# PWR-CONNS.net
KiCad netlist of a schematic drawn in Altium Designer
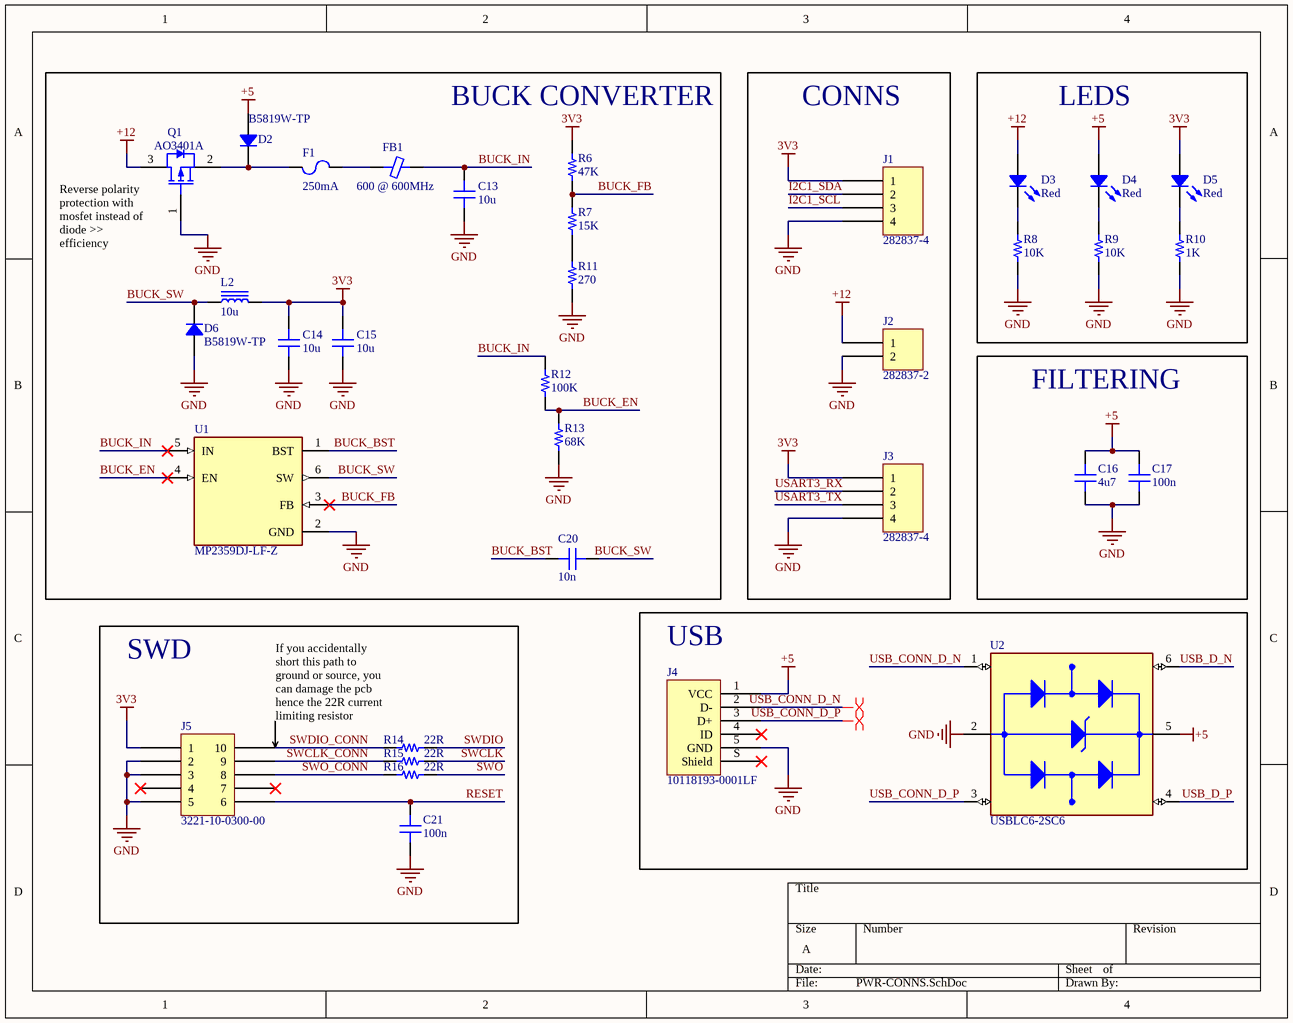
[diagram p0: PWR-CONNS.SchDoc]

(export (version "E")
  (design (tool "Eeschema 10.0.6"))
  (components
    (comp (ref "C13")
      (value "10u")
      (footprint "CAP 0805_2012")
      (description "CAP CER 2200PF 16V X7R 0805")
      (fields (field (name "PART NUMBER") "C0805C222K4RAC7800") (field (name "MANUFACTURER") "KEMET"))
      (libsource (lib "Celestial Altium Library - altium_library") (part "Capacitor"))
    )
    (comp (ref "C14")
      (value "10u")
      (footprint "CAP 0805_2012")
      (description "CAP CER 2200PF 16V X7R 0805")
      (fields (field (name "PART NUMBER") "C0805C222K4RAC7800") (field (name "MANUFACTURER") "KEMET"))
      (libsource (lib "Celestial Altium Library - altium_library") (part "Capacitor"))
    )
    (comp (ref "C15")
      (value "10u")
      (footprint "CAP 0805_2012")
      (description "CAP CER 2200PF 16V X7R 0805")
      (fields (field (name "PART NUMBER") "C0805C222K4RAC7800") (field (name "MANUFACTURER") "KEMET"))
      (libsource (lib "Celestial Altium Library - altium_library") (part "Capacitor"))
    )
    (comp (ref "C16")
      (value "4u7")
      (footprint "CAP 0603_1608")
      (description "CAP CER SMD 0603 .1UF 5% X7R 16V")
      (fields (field (name "PART NUMBER") "C0603C104J4RAC7013") (field (name "MANUFACTURER") "KEMET"))
      (libsource (lib "Celestial Altium Library - altium_library") (part "Capacitor"))
    )
    (comp (ref "C17")
      (value "100n")
      (footprint "CAP 0603_1608")
      (description "CAP CER SMD 0603 .1UF 5% X7R 16V")
      (fields (field (name "PART NUMBER") "C0603C104J4RAC7013") (field (name "MANUFACTURER") "KEMET"))
      (libsource (lib "Celestial Altium Library - altium_library") (part "Capacitor"))
    )
    (comp (ref "C20")
      (value "10n")
      (footprint "CAP 0805_2012")
      (description "CAP CER 2200PF 16V X7R 0805")
      (fields (field (name "PART NUMBER") "C0805C222K4RAC7800") (field (name "MANUFACTURER") "KEMET"))
      (libsource (lib "Celestial Altium Library - altium_library") (part "Capacitor"))
    )
    (comp (ref "C21")
      (value "100n")
      (footprint "CAP 0603_1608")
      (description "CAP CER SMD 0603 .1UF 5% X7R 16V")
      (fields (field (name "PART NUMBER") "C0603C104J4RAC7013") (field (name "MANUFACTURER") "KEMET"))
      (libsource (lib "Celestial Altium Library - altium_library") (part "Capacitor"))
    )
    (comp (ref "D2")
      (value "B5819W-TP")
      (footprint "SOD-123")
      (description "DIODE SCHOTTKY 40V 1A SOD123")
      (fields (field (name "MANUFACTURER") "Micro Commercial Co"))
      (libsource (lib "Celestial Altium Library - altium_library") (part "Diode"))
    )
    (comp (ref "D3")
      (value "Red")
      (footprint "LED 0603_1608 RED")
      (description "LED RED 0603")
      (fields (field (name "PART NUMBER") "APT1608SEC/J3-AMT") (field (name "MANUFACTURER") "Kingbright"))
      (libsource (lib "Celestial Altium Library - altium_library") (part "LED"))
    )
    (comp (ref "D4")
      (value "Red")
      (footprint "LED 0603_1608 RED")
      (description "LED RED 0603")
      (fields (field (name "PART NUMBER") "APT1608SEC/J3-AMT") (field (name "MANUFACTURER") "Kingbright"))
      (libsource (lib "Celestial Altium Library - altium_library") (part "LED"))
    )
    (comp (ref "D5")
      (value "Red")
      (footprint "LED 0603_1608 RED")
      (description "LED RED 0603")
      (fields (field (name "PART NUMBER") "APT1608SEC/J3-AMT") (field (name "MANUFACTURER") "Kingbright"))
      (libsource (lib "Celestial Altium Library - altium_library") (part "LED"))
    )
    (comp (ref "D6")
      (value "B5819W-TP")
      (footprint "SOD-123")
      (description "DIODE SCHOTTKY 40V 1A SOD123")
      (fields (field (name "MANUFACTURER") "Micro Commercial Co"))
      (libsource (lib "Celestial Altium Library - altium_library") (part "Diode"))
    )
    (comp (ref "F1")
      (value "250mA")
      (footprint "FUSE 1206_3216 0.6MM")
      (description "FUSE BOARD MNT 500MA 63VDC 1206")
      (fields (field (name "PART NUMBER") "SF-1206FP050-2") (field (name "MANUFACTURER") "Bourns Inc."))
      (libsource (lib "Celestial Altium Library - altium_library") (part "MOUNTED FUSE"))
    )
    (comp (ref "FB1")
      (value "600 @ 600MHz")
      (footprint "FER 0402_1005")
      (description "FERRITE BEAD 600 OHM 0402 1LN")
      (fields (field (name "PART NUMBER") "Z0402C601ESMST") (field (name "MANUFACTURER") "KEMET"))
      (libsource (lib "Celestial Altium Library - altium_library") (part "Ferrite Chip"))
    )
    (comp (ref "J1")
      (value "282837-4")
      (footprint "TE 282837-4")
      (description "TERM BLK 4P SIDE ENT 5.08MM PCB")
      (fields (field (name "MANUFACTURER") "TE Connectivity AMP Connectors") (field (name "VOLTAGE") "300 V"))
      (libsource (lib "Celestial Altium Library - altium_library") (part "4 Pin"))
    )
    (comp (ref "J2")
      (value "282837-2")
      (footprint "TE 282837-2")
      (description "TERM BLK 2P SIDE ENT 5.08MM PCB")
      (fields (field (name "MANUFACTURER") "TE Connectivity AMP Connectors") (field (name "VOLTAGE") "300 V"))
      (libsource (lib "Celestial Altium Library - altium_library") (part "2 Pin"))
    )
    (comp (ref "J3")
      (value "282837-4")
      (footprint "TE 282837-4")
      (description "TERM BLK 4P SIDE ENT 5.08MM PCB")
      (fields (field (name "MANUFACTURER") "TE Connectivity AMP Connectors") (field (name "VOLTAGE") "300 V"))
      (libsource (lib "Celestial Altium Library - altium_library") (part "4 Pin"))
    )
    (comp (ref "J4")
      (value "10118193-0001LF")
      (footprint "FCI USB 10118193-0001LF")
      (description "CONN RCPT USB2.0 MICRO B SMD R/A")
      (fields (field (name "MANUFACTURER") "Amphenol ICC (FCI)"))
      (libsource (lib "Celestial Altium Library - altium_library") (part "USB 2.0 Type B Micro"))
    )
    (comp (ref "J5")
      (value "3221-10-0300-00")
      (footprint "CNC TECH 3221-10-0300-00")
      (description "CONN HEADER SMD 10POS 1.27MM")
      (fields (field (name "MANUFACTURER") "CNC Tech"))
      (libsource (lib "Celestial Altium Library - altium_library") (part "2x5 Pin"))
    )
    (comp (ref "L2")
      (value "10u")
      (footprint "BOURNS SRP5030T")
      (description "FIXED IND 10UH 2.75A 128MOHM SMD")
      (fields (field (name "PART NUMBER") "SRP5030T-100M") (field (name "MANUFACTURER") "Bourns Inc."))
      (libsource (lib "Celestial Altium Library - altium_library") (part "Inductor"))
    )
    (comp (ref "Q1")
      (value "AO3401A")
      (footprint "AO-SOT-23-3L_V")
      (description "P-Channel MOSFET, 30 V, 4 A, -55 to 150 degC, 3-Pin SOT-23-3L, RoHS, Tape and Reel")
      (fields (field (name "MANUFACTURER") "Alpha and Omega"))
      (libsource (lib "Altium Content Vault") (part "PEMOS-GSD-3"))
    )
    (comp (ref "R6")
      (value "47K")
      (footprint "RES 0603_1608")
      (description "RES SMD 47 OHM 1% 1/10W 0603")
      (fields (field (name "PART NUMBER") "AC0603FR-0747RL") (field (name "MANUFACTURER") "Yageo"))
      (libsource (lib "Celestial Altium Library - altium_library") (part "Resistor"))
    )
    (comp (ref "R7")
      (value "15K")
      (footprint "RES 0603_1608")
      (description "RES SMD 47 OHM 1% 1/10W 0603")
      (fields (field (name "PART NUMBER") "AC0603FR-0747RL") (field (name "MANUFACTURER") "Yageo"))
      (libsource (lib "Celestial Altium Library - altium_library") (part "Resistor"))
    )
    (comp (ref "R8")
      (value "10K")
      (footprint "RES 0603_1608")
      (description "RES SMD 47 OHM 1% 1/10W 0603")
      (fields (field (name "PART NUMBER") "AC0603FR-0747RL") (field (name "MANUFACTURER") "Yageo"))
      (libsource (lib "Celestial Altium Library - altium_library") (part "Resistor"))
    )
    (comp (ref "R9")
      (value "10K")
      (footprint "RES 0603_1608")
      (description "RES SMD 47 OHM 1% 1/10W 0603")
      (fields (field (name "PART NUMBER") "AC0603FR-0747RL") (field (name "MANUFACTURER") "Yageo"))
      (libsource (lib "Celestial Altium Library - altium_library") (part "Resistor"))
    )
    (comp (ref "R10")
      (value "1K")
      (footprint "RES 0603_1608")
      (description "RES SMD 47 OHM 1% 1/10W 0603")
      (fields (field (name "PART NUMBER") "AC0603FR-0747RL") (field (name "MANUFACTURER") "Yageo"))
      (libsource (lib "Celestial Altium Library - altium_library") (part "Resistor"))
    )
    (comp (ref "R11")
      (value "270")
      (footprint "RES 0603_1608")
      (description "RES SMD 47 OHM 1% 1/10W 0603")
      (fields (field (name "PART NUMBER") "AC0603FR-0747RL") (field (name "MANUFACTURER") "Yageo"))
      (libsource (lib "Celestial Altium Library - altium_library") (part "Resistor"))
    )
    (comp (ref "R12")
      (value "100K")
      (footprint "RES 0603_1608")
      (description "RES SMD 47 OHM 1% 1/10W 0603")
      (fields (field (name "PART NUMBER") "AC0603FR-0747RL") (field (name "MANUFACTURER") "Yageo"))
      (libsource (lib "Celestial Altium Library - altium_library") (part "Resistor"))
    )
    (comp (ref "R13")
      (value "68K")
      (footprint "RES 0603_1608")
      (description "RES SMD 47 OHM 1% 1/10W 0603")
      (fields (field (name "PART NUMBER") "AC0603FR-0747RL") (field (name "MANUFACTURER") "Yageo"))
      (libsource (lib "Celestial Altium Library - altium_library") (part "Resistor"))
    )
    (comp (ref "R14")
      (value "22R")
      (footprint "RES 0603_1608")
      (description "RES SMD 47 OHM 1% 1/10W 0603")
      (fields (field (name "PART NUMBER") "AC0603FR-0747RL") (field (name "MANUFACTURER") "Yageo"))
      (libsource (lib "Celestial Altium Library - altium_library") (part "Resistor"))
    )
    (comp (ref "R15")
      (value "22R")
      (footprint "RES 0603_1608")
      (description "RES SMD 47 OHM 1% 1/10W 0603")
      (fields (field (name "PART NUMBER") "AC0603FR-0747RL") (field (name "MANUFACTURER") "Yageo"))
      (libsource (lib "Celestial Altium Library - altium_library") (part "Resistor"))
    )
    (comp (ref "R16")
      (value "22R")
      (footprint "RES 0603_1608")
      (description "RES SMD 47 OHM 1% 1/10W 0603")
      (fields (field (name "PART NUMBER") "AC0603FR-0747RL") (field (name "MANUFACTURER") "Yageo"))
      (libsource (lib "Celestial Altium Library - altium_library") (part "Resistor"))
    )
    (comp (ref "U1")
      (value "MP2359DJ-LF-Z")
      (footprint "SOT95P280X100-6N")
      (description "Buck Switching Regulator IC Positive Adjustable 0.81V 1 Output 1.2A SOT-23-6 Thin, TSOT-23-6")
      (fields (field (name "MF") "Monolithic Power"))
      (libsource (lib "MP2359DJ-LF-Z") (part "MP2359DJ-LF-Z"))
    )
    (comp (ref "U2")
      (value "USBLC6-2SC6")
      (footprint "SOT95P280X145-6N")
      (description "17V Clamp 5A (8/20Âµs) Ipp Tvs Diode Surface Mount SOT-23-6")
      (fields (field (name "MF") "STMicroelectronics"))
      (libsource (lib "USBLC6-2SC6") (part "USBLC6-2SC6"))
    )
  )
  (nets
    (net (code "1") (name "+5") (class "Default")
      (node (ref "C16") (pin "1") (pinfunction "1_1") (pintype "passive"))
      (node (ref "C17") (pin "1") (pinfunction "1_1") (pintype "passive"))
      (node (ref "D2") (pin "1") (pinfunction "1_1") (pintype "passive"))
      (node (ref "D4") (pin "1") (pinfunction "1_1") (pintype "passive"))
      (node (ref "J4") (pin "1") (pinfunction "VCC_1") (pintype "passive"))
      (node (ref "U2") (pin "5") (pinfunction "VBUS_5") (pintype "power_in"))
    )
    (net (code "2") (name "+12") (class "Default")
      (node (ref "D3") (pin "1") (pinfunction "1_1") (pintype "passive"))
      (node (ref "J2") (pin "1") (pinfunction "1_1") (pintype "passive"))
      (node (ref "Q1") (pin "3") (pinfunction "DRAIN_3") (pintype "passive"))
    )
    (net (code "3") (name "/BUCK_BST") (class "Default")
      (node (ref "C20") (pin "2") (pinfunction "2_2") (pintype "passive"))
      (node (ref "U1") (pin "1") (pinfunction "BST_1") (pintype "passive"))
    )
    (net (code "4") (name "/BUCK_EN") (class "Default")
      (node (ref "R12") (pin "1") (pinfunction "1_1") (pintype "passive"))
      (node (ref "R13") (pin "2") (pinfunction "2_2") (pintype "passive"))
      (node (ref "U1") (pin "4") (pinfunction "EN_4") (pintype "input"))
    )
    (net (code "5") (name "/BUCK_FB") (class "Default")
      (node (ref "R6") (pin "1") (pinfunction "1_1") (pintype "passive"))
      (node (ref "R7") (pin "2") (pinfunction "2_2") (pintype "passive"))
      (node (ref "U1") (pin "3") (pinfunction "FB_3") (pintype "input"))
    )
    (net (code "6") (name "/BUCK_IN") (class "Default")
      (node (ref "C13") (pin "2") (pinfunction "2_2") (pintype "passive"))
      (node (ref "FB1") (pin "2") (pinfunction "2_2") (pintype "passive"))
      (node (ref "R12") (pin "2") (pinfunction "2_2") (pintype "passive"))
      (node (ref "U1") (pin "5") (pinfunction "IN_5") (pintype "input"))
    )
    (net (code "7") (name "/BUCK_SW") (class "Default")
      (node (ref "C20") (pin "1") (pinfunction "1_1") (pintype "passive"))
      (node (ref "D6") (pin "2") (pinfunction "2_2") (pintype "passive"))
      (node (ref "L2") (pin "1") (pinfunction "1_1") (pintype "passive"))
      (node (ref "U1") (pin "6") (pinfunction "SW_6") (pintype "output"))
    )
    (net (code "8") (name "/I2C1_SCL") (class "Default")
      (node (ref "J1") (pin "3") (pinfunction "3_3") (pintype "passive"))
    )
    (net (code "9") (name "/I2C1_SDA") (class "Default")
      (node (ref "J1") (pin "2") (pinfunction "2_2") (pintype "passive"))
    )
    (net (code "10") (name "/RESET") (class "Default")
      (node (ref "C21") (pin "1") (pinfunction "1_1") (pintype "passive"))
      (node (ref "J5") (pin "6") (pinfunction "6_6") (pintype "passive"))
    )
    (net (code "11") (name "/SWCLK") (class "Default")
      (node (ref "R15") (pin "1") (pinfunction "1_1") (pintype "passive"))
    )
    (net (code "12") (name "/SWCLK_CONN") (class "Default")
      (node (ref "J5") (pin "9") (pinfunction "9_9") (pintype "passive"))
      (node (ref "R15") (pin "2") (pinfunction "2_2") (pintype "passive"))
    )
    (net (code "13") (name "/SWDIO") (class "Default")
      (node (ref "R14") (pin "1") (pinfunction "1_1") (pintype "passive"))
    )
    (net (code "14") (name "/SWDIO_CONN") (class "Default")
      (node (ref "J5") (pin "10") (pinfunction "10_10") (pintype "passive"))
      (node (ref "R14") (pin "2") (pinfunction "2_2") (pintype "passive"))
    )
    (net (code "15") (name "/SWO") (class "Default")
      (node (ref "R16") (pin "1") (pinfunction "1_1") (pintype "passive"))
    )
    (net (code "16") (name "/SWO_CONN") (class "Default")
      (node (ref "J5") (pin "8") (pinfunction "8_8") (pintype "passive"))
      (node (ref "R16") (pin "2") (pinfunction "2_2") (pintype "passive"))
    )
    (net (code "17") (name "/USART3_RX") (class "Default")
      (node (ref "J3") (pin "2") (pinfunction "2_2") (pintype "passive"))
    )
    (net (code "18") (name "/USART3_TX") (class "Default")
      (node (ref "J3") (pin "3") (pinfunction "3_3") (pintype "passive"))
    )
    (net (code "19") (name "/USB_CONN_D_N") (class "Default")
      (node (ref "J4") (pin "2") (pinfunction "D-_2") (pintype "passive"))
      (node (ref "U2") (pin "1") (pinfunction "I/O1_IN_1") (pintype "bidirectional"))
    )
    (net (code "20") (name "/USB_CONN_D_P") (class "Default")
      (node (ref "J4") (pin "3") (pinfunction "D+_3") (pintype "passive"))
      (node (ref "U2") (pin "3") (pinfunction "I/O2_IN_3") (pintype "bidirectional"))
    )
    (net (code "21") (name "/USB_D_N") (class "Default")
      (node (ref "U2") (pin "6") (pinfunction "I/O1_OUT_6") (pintype "bidirectional"))
    )
    (net (code "22") (name "/USB_D_P") (class "Default")
      (node (ref "U2") (pin "4") (pinfunction "I/O2_OUT_4") (pintype "bidirectional"))
    )
    (net (code "23") (name "3V3") (class "Default")
      (node (ref "C14") (pin "2") (pinfunction "2_2") (pintype "passive"))
      (node (ref "C15") (pin "2") (pinfunction "2_2") (pintype "passive"))
      (node (ref "D5") (pin "1") (pinfunction "1_1") (pintype "passive"))
      (node (ref "J1") (pin "1") (pinfunction "1_1") (pintype "passive"))
      (node (ref "J3") (pin "1") (pinfunction "1_1") (pintype "passive"))
      (node (ref "J5") (pin "1") (pinfunction "1_1") (pintype "passive"))
      (node (ref "L2") (pin "2") (pinfunction "2_2") (pintype "passive"))
      (node (ref "R6") (pin "2") (pinfunction "2_2") (pintype "passive"))
    )
    (net (code "24") (name "GND") (class "Default")
      (node (ref "C13") (pin "1") (pinfunction "1_1") (pintype "passive"))
      (node (ref "C14") (pin "1") (pinfunction "1_1") (pintype "passive"))
      (node (ref "C15") (pin "1") (pinfunction "1_1") (pintype "passive"))
      (node (ref "C16") (pin "2") (pinfunction "2_2") (pintype "passive"))
      (node (ref "C17") (pin "2") (pinfunction "2_2") (pintype "passive"))
      (node (ref "C21") (pin "2") (pinfunction "2_2") (pintype "passive"))
      (node (ref "D6") (pin "1") (pinfunction "1_1") (pintype "passive"))
      (node (ref "J1") (pin "4") (pinfunction "4_4") (pintype "passive"))
      (node (ref "J2") (pin "2") (pinfunction "2_2") (pintype "passive"))
      (node (ref "J3") (pin "4") (pinfunction "4_4") (pintype "passive"))
      (node (ref "J4") (pin "5") (pinfunction "GND_5") (pintype "passive"))
      (node (ref "J5") (pin "2") (pinfunction "2_2") (pintype "passive"))
      (node (ref "J5") (pin "3") (pinfunction "3_3") (pintype "passive"))
      (node (ref "J5") (pin "5") (pinfunction "5_5") (pintype "passive"))
      (node (ref "Q1") (pin "1") (pinfunction "GATE_1") (pintype "passive"))
      (node (ref "R10") (pin "1") (pinfunction "1_1") (pintype "passive"))
      (node (ref "R11") (pin "1") (pinfunction "1_1") (pintype "passive"))
      (node (ref "R13") (pin "1") (pinfunction "1_1") (pintype "passive"))
      (node (ref "R8") (pin "1") (pinfunction "1_1") (pintype "passive"))
      (node (ref "R9") (pin "1") (pinfunction "1_1") (pintype "passive"))
      (node (ref "U1") (pin "2") (pinfunction "GND_2") (pintype "power_in"))
      (node (ref "U2") (pin "2") (pinfunction "GND_2") (pintype "power_in"))
    )
    (net (code "25") (name "Net-(D3-Pad2)") (class "Default")
      (node (ref "D3") (pin "2") (pinfunction "2_2") (pintype "passive"))
      (node (ref "R8") (pin "2") (pinfunction "2_2") (pintype "passive"))
    )
    (net (code "26") (name "Net-(D4-Pad2)") (class "Default")
      (node (ref "D4") (pin "2") (pinfunction "2_2") (pintype "passive"))
      (node (ref "R9") (pin "2") (pinfunction "2_2") (pintype "passive"))
    )
    (net (code "27") (name "Net-(D5-Pad2)") (class "Default")
      (node (ref "D5") (pin "2") (pinfunction "2_2") (pintype "passive"))
      (node (ref "R10") (pin "2") (pinfunction "2_2") (pintype "passive"))
    )
    (net (code "28") (name "Net-(F1-Pad2)") (class "Default")
      (node (ref "F1") (pin "2") (pintype "passive"))
      (node (ref "FB1") (pin "1") (pinfunction "1_1") (pintype "passive"))
    )
    (net (code "29") (name "Net-(Q1-SOURCE)") (class "Default")
      (node (ref "D2") (pin "2") (pinfunction "2_2") (pintype "passive"))
      (node (ref "F1") (pin "1") (pintype "passive"))
      (node (ref "Q1") (pin "2") (pinfunction "SOURCE_2") (pintype "passive"))
    )
    (net (code "30") (name "Net-(R11-Pad2)") (class "Default")
      (node (ref "R11") (pin "2") (pinfunction "2_2") (pintype "passive"))
      (node (ref "R7") (pin "1") (pinfunction "1_1") (pintype "passive"))
    )
    (net (code "31") (name "unconnected-(J4-ID-Pad4)") (class "Default")
      (node (ref "J4") (pin "4") (pinfunction "ID_4") (pintype "passive+no_connect"))
    )
    (net (code "32") (name "unconnected-(J4-Shield-PadS)") (class "Default")
      (node (ref "J4") (pin "S") (pinfunction "Shield_S") (pintype "passive+no_connect"))
    )
    (net (code "33") (name "unconnected-(J5-Pad4)") (class "Default")
      (node (ref "J5") (pin "4") (pinfunction "4_4") (pintype "passive+no_connect"))
    )
    (net (code "34") (name "unconnected-(J5-Pad7)") (class "Default")
      (node (ref "J5") (pin "7") (pinfunction "7_7") (pintype "passive+no_connect"))
    )
  )
)
